# USB_ISO_FS_00.net
KiCad netlist of a schematic drawn in Altium Designer
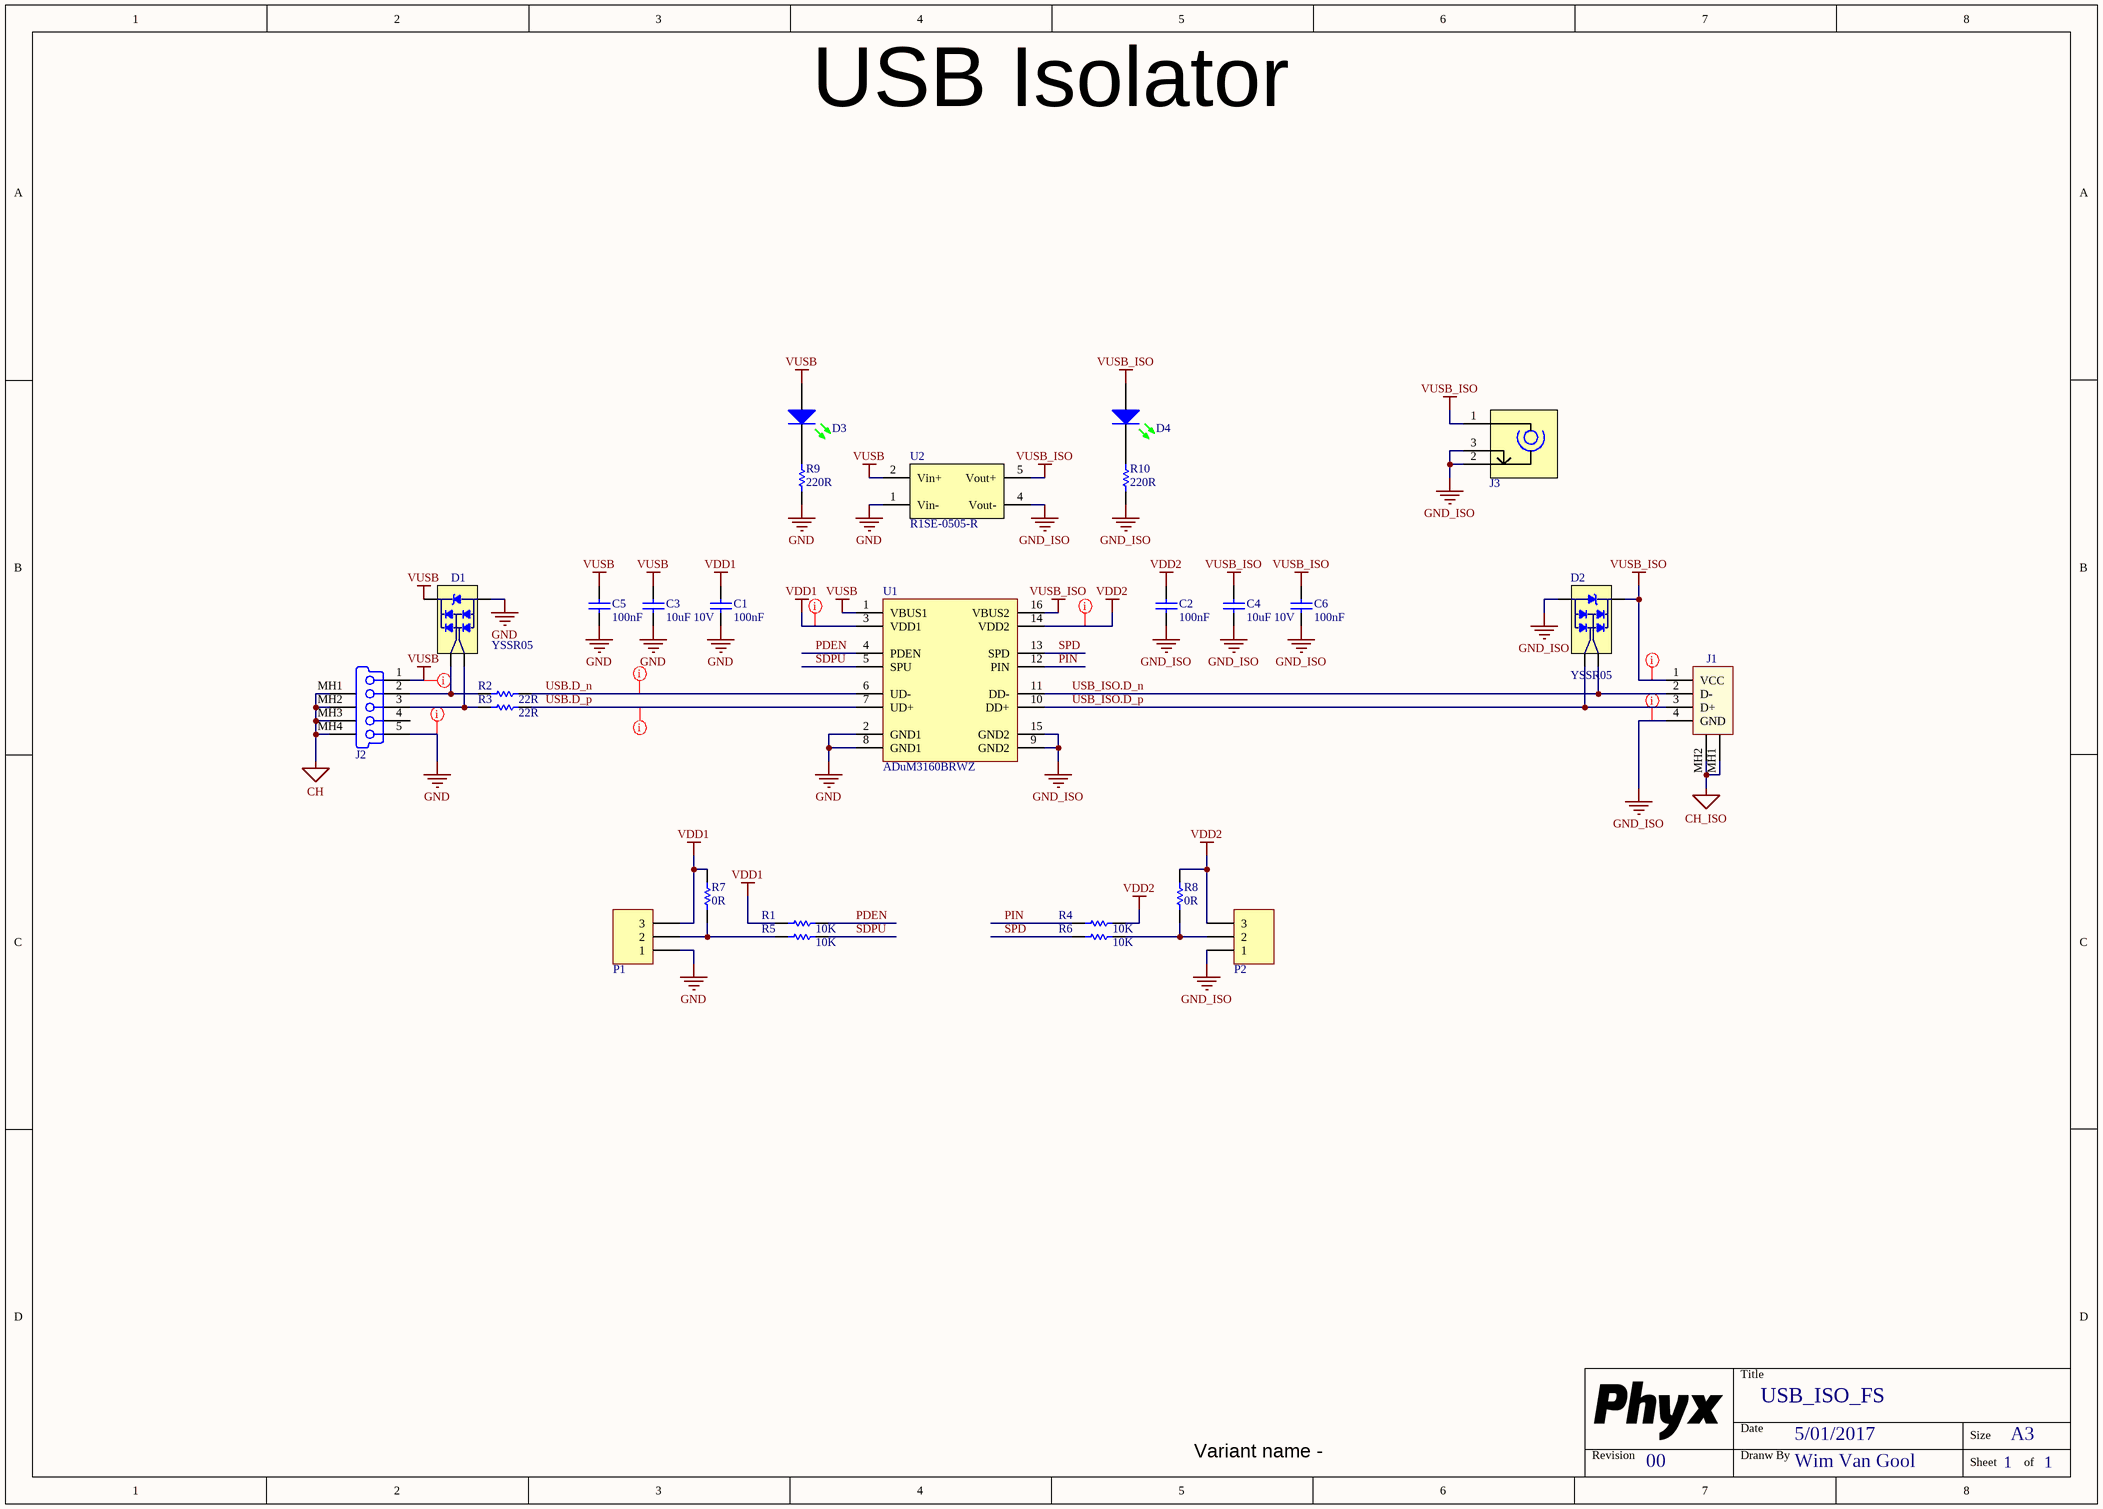
[diagram p0: USB_ISO_FS_00.SchDoc]

(export (version "E")
  (design (tool "Eeschema 10.0.6"))
  (components
    (comp (ref "C1")
      (value "100nF")
      (footprint "C0603_N")
      (description "CAP # 100nF 16V 0603")
      (fields (field (name "Comment") "CAP_CERAMIC"))
      (libsource (lib "Phyx_Components") (part "CAP_CERAMIC"))
    )
    (comp (ref "C2")
      (value "100nF")
      (footprint "C0603_N")
      (description "CAP # 100nF 16V 0603")
      (fields (field (name "Comment") "CAP_CERAMIC"))
      (libsource (lib "Phyx_Components") (part "CAP_CERAMIC"))
    )
    (comp (ref "C3")
      (value "10uF 10V")
      (footprint "C0805_N")
      (description "CAP # 10uF 10V 0805")
      (fields (field (name "Comment") "CAP_CERAMIC"))
      (libsource (lib "Phyx_Components") (part "CAP_CERAMIC"))
    )
    (comp (ref "C4")
      (value "10uF 10V")
      (footprint "C0805_N")
      (description "CAP # 10uF 10V 0805")
      (fields (field (name "Comment") "CAP_CERAMIC"))
      (libsource (lib "Phyx_Components") (part "CAP_CERAMIC"))
    )
    (comp (ref "C5")
      (value "100nF")
      (footprint "C0603_N")
      (description "CAP # 100nF 16V 0603")
      (fields (field (name "Comment") "CAP_CERAMIC"))
      (libsource (lib "Phyx_Components") (part "CAP_CERAMIC"))
    )
    (comp (ref "C6")
      (value "100nF")
      (footprint "C0603_N")
      (description "CAP # 100nF 16V 0603")
      (fields (field (name "Comment") "CAP_CERAMIC"))
      (libsource (lib "Phyx_Components") (part "CAP_CERAMIC"))
    )
    (comp (ref "D1")
      (value "YSSR05")
      (footprint "SOT-143")
      (description "=Description")
      (fields (field (name "Comment") "Low Capacitanse TVS Diode array"))
      (libsource (lib "") (part "YSSR05_1"))
    )
    (comp (ref "D2")
      (value "YSSR05")
      (footprint "SOT-143")
      (description "=Description")
      (fields (field (name "Comment") "Low Capacitanse TVS Diode array"))
      (libsource (lib "Phyx_Components") (part "YSSR05"))
    )
    (comp (ref "D3")
      (value "Default 0805 Green LED")
      (footprint "LED_0805_GR")
      (description "LED # Green 0805")
      (libsource (lib "Phyx_Components") (part "LED_GREEN"))
    )
    (comp (ref "D4")
      (value "Default 0805 Green LED")
      (footprint "LED_0805_GR")
      (description "LED # Green 0805")
      (libsource (lib "Phyx_Components") (part "LED_GREEN"))
    )
    (comp (ref "J1")
      (value "USB type A Short horizontal connector")
      (footprint "WE_614104150121")
      (description "USB A 614104150121 Short")
      (libsource (lib "Phyx_Components") (part "USB_A"))
    )
    (comp (ref "J2")
      (value "THT USB Mini-B Receptacle")
      (footprint "USB_Mini-B_THT")
      (description "USB Mini-B F")
      (libsource (lib "Phyx_Components") (part "USB_OTG_Mini-B"))
    )
    (comp (ref "J3")
      (value "Socket RA 3.5 with 1.35 barrel")
      (footprint "DC-003")
      (description "SCKT 1.35mm barrel 3.5mm dia")
      (libsource (lib "Phyx_Components") (part "Cliff_DC10"))
    )
    (comp (ref "P1")
      (value "Header 3")
      (footprint "HDR1X3")
      (description "Pin Header 2.54mm 3way")
      (libsource (lib "") (part "Header 3_1"))
    )
    (comp (ref "P2")
      (value "Header 3")
      (footprint "HDR1X3")
      (description "Pin Header 2.54mm 3way")
      (libsource (lib "Phyx_Components") (part "Header 3"))
    )
    (comp (ref "R1")
      (value "10K")
      (footprint "R0603_N")
      (description "RES # 10K 0603")
      (fields (field (name "Comment") "RESISTOR"))
      (libsource (lib "Phyx_Components") (part "RESISTOR"))
    )
    (comp (ref "R2")
      (value "22R")
      (footprint "R0603_N")
      (description "RES # 22R 0603")
      (fields (field (name "Comment") "RESISTOR"))
      (libsource (lib "Phyx_Components") (part "RESISTOR"))
    )
    (comp (ref "R3")
      (value "22R")
      (footprint "R0603_N")
      (description "RES # 22R 0603")
      (fields (field (name "Comment") "RESISTOR"))
      (libsource (lib "Phyx_Components") (part "RESISTOR"))
    )
    (comp (ref "R4")
      (value "10K")
      (footprint "R0603_N")
      (description "RES # 10K 0603")
      (fields (field (name "Comment") "RESISTOR"))
      (libsource (lib "Phyx_Components") (part "RESISTOR"))
    )
    (comp (ref "R5")
      (value "10K")
      (footprint "R0603_N")
      (description "RES # 10K 0603")
      (fields (field (name "Comment") "RESISTOR"))
      (libsource (lib "Phyx_Components") (part "RESISTOR"))
    )
    (comp (ref "R6")
      (value "10K")
      (footprint "R0603_N")
      (description "RES # 10K 0603")
      (fields (field (name "Comment") "RESISTOR"))
      (libsource (lib "Phyx_Components") (part "RESISTOR"))
    )
    (comp (ref "R7")
      (value "0R")
      (footprint "R0603_N")
      (description "RES # 0R 0603")
      (fields (field (name "Comment") "RESISTOR"))
      (libsource (lib "Phyx_Components") (part "RESISTOR"))
    )
    (comp (ref "R8")
      (value "0R")
      (footprint "R0603_N")
      (description "RES # 0R 0603")
      (fields (field (name "Comment") "RESISTOR"))
      (libsource (lib "Phyx_Components") (part "RESISTOR"))
    )
    (comp (ref "R9")
      (value "220R")
      (footprint "R0603_N")
      (description "RES # 220R 0603")
      (fields (field (name "Comment") "RESISTOR"))
      (libsource (lib "Phyx_Components") (part "RESISTOR"))
    )
    (comp (ref "R10")
      (value "220R")
      (footprint "R0603_N")
      (description "RES # 220R 0603")
      (fields (field (name "Comment") "RESISTOR"))
      (libsource (lib "Phyx_Components") (part "RESISTOR"))
    )
    (comp (ref "U1")
      (value "ADuM3160BRWZ")
      (footprint "SOIC_W_16")
      (description "ISO # USB ADuM3160BRWZ")
      (fields (field (name "Comment") "USB FS 12Mbps isolator 2,5kV"))
      (libsource (lib "Phyx_Components") (part "ADUM3160"))
    )
    (comp (ref "U2")
      (value "R1SE-0505-R")
      (footprint "R1SE-0505-R")
      (description "ISO # PWR 5V 1W 1kV R1SE-0505-R")
      (fields (field (name "Comment") "Isolated DC-DC module 1kV 5V 1W"))
      (libsource (lib "Phyx_Components") (part "R1SE-0505-R"))
    )
  )
  (nets
    (net (code "1") (name "/PDEN") (class "Default")
      (node (ref "R1") (pin "1") (pinfunction "1_1") (pintype "passive"))
      (node (ref "U1") (pin "4") (pinfunction "PDEN_4") (pintype "passive"))
    )
    (net (code "2") (name "/PIN") (class "Default")
      (node (ref "R4") (pin "2") (pinfunction "2_2") (pintype "passive"))
      (node (ref "U1") (pin "12") (pinfunction "PIN_12") (pintype "passive"))
    )
    (net (code "3") (name "/SDPU") (class "Default")
      (node (ref "R5") (pin "1") (pinfunction "1_1") (pintype "passive"))
      (node (ref "U1") (pin "5") (pinfunction "SPU_5") (pintype "passive"))
    )
    (net (code "4") (name "/SPD") (class "Default")
      (node (ref "R6") (pin "2") (pinfunction "2_2") (pintype "passive"))
      (node (ref "U1") (pin "13") (pinfunction "SPD_13") (pintype "passive"))
    )
    (net (code "5") (name "/USB.D_n") (class "Default")
      (node (ref "R2") (pin "1") (pinfunction "1_1") (pintype "passive"))
      (node (ref "U1") (pin "6") (pinfunction "UD-_6") (pintype "passive"))
    )
    (net (code "6") (name "/USB.D_p") (class "Default")
      (node (ref "R3") (pin "1") (pinfunction "1_1") (pintype "passive"))
      (node (ref "U1") (pin "7") (pinfunction "UD+_7") (pintype "passive"))
    )
    (net (code "7") (name "/USB_ISO.D_n") (class "Default")
      (node (ref "D2") (pin "3") (pinfunction "3_3") (pintype "passive"))
      (node (ref "J1") (pin "2") (pinfunction "D-_2") (pintype "passive"))
      (node (ref "U1") (pin "11") (pinfunction "DD-_11") (pintype "passive"))
    )
    (net (code "8") (name "/USB_ISO.D_p") (class "Default")
      (node (ref "D2") (pin "2") (pinfunction "2_2") (pintype "passive"))
      (node (ref "J1") (pin "3") (pinfunction "D+_3") (pintype "passive"))
      (node (ref "U1") (pin "10") (pinfunction "DD+_10") (pintype "passive"))
    )
    (net (code "9") (name "CH") (class "Default")
      (node (ref "J2") (pin "MH1") (pinfunction "Tab_MH1") (pintype "passive"))
      (node (ref "J2") (pin "MH2") (pinfunction "Tab_MH2") (pintype "passive"))
      (node (ref "J2") (pin "MH3") (pinfunction "Tab_MH3") (pintype "passive"))
      (node (ref "J2") (pin "MH4") (pinfunction "Tab_MH4") (pintype "passive"))
    )
    (net (code "10") (name "CH_ISO") (class "Default")
      (node (ref "J1") (pin "MH1") (pinfunction "Tab_MH1") (pintype "passive"))
      (node (ref "J1") (pin "MH2") (pinfunction "Tab_MH2") (pintype "passive"))
    )
    (net (code "11") (name "GND") (class "Default")
      (node (ref "C1") (pin "2") (pinfunction "2_2") (pintype "passive"))
      (node (ref "C3") (pin "2") (pinfunction "2_2") (pintype "passive"))
      (node (ref "C5") (pin "2") (pinfunction "2_2") (pintype "passive"))
      (node (ref "D1") (pin "1") (pinfunction "1_1") (pintype "passive"))
      (node (ref "J2") (pin "5") (pinfunction "GND_5") (pintype "passive"))
      (node (ref "P1") (pin "1") (pinfunction "1_1") (pintype "passive"))
      (node (ref "R9") (pin "2") (pinfunction "2_2") (pintype "passive"))
      (node (ref "U1") (pin "2") (pinfunction "GND1_2") (pintype "passive"))
      (node (ref "U1") (pin "8") (pinfunction "GND1_8") (pintype "passive"))
      (node (ref "U2") (pin "1") (pinfunction "Vin-_1") (pintype "power_in"))
    )
    (net (code "12") (name "GND_ISO") (class "Default")
      (node (ref "C2") (pin "2") (pinfunction "2_2") (pintype "passive"))
      (node (ref "C4") (pin "2") (pinfunction "2_2") (pintype "passive"))
      (node (ref "C6") (pin "2") (pinfunction "2_2") (pintype "passive"))
      (node (ref "D2") (pin "1") (pinfunction "1_1") (pintype "passive"))
      (node (ref "J1") (pin "4") (pinfunction "GND_4") (pintype "passive"))
      (node (ref "J3") (pin "2") (pinfunction "2_2") (pintype "passive"))
      (node (ref "J3") (pin "3") (pinfunction "3_3") (pintype "passive"))
      (node (ref "P2") (pin "1") (pinfunction "1_1") (pintype "passive"))
      (node (ref "R10") (pin "2") (pinfunction "2_2") (pintype "passive"))
      (node (ref "U1") (pin "15") (pinfunction "GND2_15") (pintype "passive"))
      (node (ref "U1") (pin "9") (pinfunction "GND2_9") (pintype "passive"))
      (node (ref "U2") (pin "4") (pinfunction "Vout-_4") (pintype "power_in"))
    )
    (net (code "13") (name "Net-(D3-K)") (class "Default")
      (node (ref "D3") (pin "2") (pinfunction "K_2") (pintype "passive"))
      (node (ref "R9") (pin "1") (pinfunction "1_1") (pintype "passive"))
    )
    (net (code "14") (name "Net-(D4-K)") (class "Default")
      (node (ref "D4") (pin "2") (pinfunction "K_2") (pintype "passive"))
      (node (ref "R10") (pin "1") (pinfunction "1_1") (pintype "passive"))
    )
    (net (code "15") (name "Net-(J2-D+)") (class "Default")
      (node (ref "D1") (pin "2") (pinfunction "2_2") (pintype "passive"))
      (node (ref "J2") (pin "3") (pinfunction "D+_3") (pintype "passive"))
      (node (ref "R3") (pin "2") (pinfunction "2_2") (pintype "passive"))
    )
    (net (code "16") (name "Net-(J2-D-)") (class "Default")
      (node (ref "D1") (pin "3") (pinfunction "3_3") (pintype "passive"))
      (node (ref "J2") (pin "2") (pinfunction "D-_2") (pintype "passive"))
      (node (ref "R2") (pin "2") (pinfunction "2_2") (pintype "passive"))
    )
    (net (code "17") (name "Net-(P1-Pad2)") (class "Default")
      (node (ref "P1") (pin "2") (pinfunction "2_2") (pintype "passive"))
      (node (ref "R5") (pin "2") (pinfunction "2_2") (pintype "passive"))
      (node (ref "R7") (pin "2") (pinfunction "2_2") (pintype "passive"))
    )
    (net (code "18") (name "Net-(P2-Pad2)") (class "Default")
      (node (ref "P2") (pin "2") (pinfunction "2_2") (pintype "passive"))
      (node (ref "R6") (pin "1") (pinfunction "1_1") (pintype "passive"))
      (node (ref "R8") (pin "2") (pinfunction "2_2") (pintype "passive"))
    )
    (net (code "19") (name "VDD1") (class "Default")
      (node (ref "C1") (pin "1") (pinfunction "1_1") (pintype "passive"))
      (node (ref "P1") (pin "3") (pinfunction "3_3") (pintype "passive"))
      (node (ref "R1") (pin "2") (pinfunction "2_2") (pintype "passive"))
      (node (ref "R7") (pin "1") (pinfunction "1_1") (pintype "passive"))
      (node (ref "U1") (pin "3") (pinfunction "VDD1_3") (pintype "passive"))
    )
    (net (code "20") (name "VDD2") (class "Default")
      (node (ref "C2") (pin "1") (pinfunction "1_1") (pintype "passive"))
      (node (ref "P2") (pin "3") (pinfunction "3_3") (pintype "passive"))
      (node (ref "R4") (pin "1") (pinfunction "1_1") (pintype "passive"))
      (node (ref "R8") (pin "1") (pinfunction "1_1") (pintype "passive"))
      (node (ref "U1") (pin "14") (pinfunction "VDD2_14") (pintype "passive"))
    )
    (net (code "21") (name "VUSB") (class "Default")
      (node (ref "C3") (pin "1") (pinfunction "1_1") (pintype "passive"))
      (node (ref "C5") (pin "1") (pinfunction "1_1") (pintype "passive"))
      (node (ref "D1") (pin "4") (pinfunction "4_4") (pintype "passive"))
      (node (ref "D3") (pin "1") (pinfunction "A_1") (pintype "passive"))
      (node (ref "J2") (pin "1") (pinfunction "V_BUS_(5V)_1") (pintype "passive"))
      (node (ref "U1") (pin "1") (pinfunction "VBUS1_1") (pintype "passive"))
      (node (ref "U2") (pin "2") (pinfunction "Vin+_2") (pintype "power_in"))
    )
    (net (code "22") (name "VUSB_ISO") (class "Default")
      (node (ref "C4") (pin "1") (pinfunction "1_1") (pintype "passive"))
      (node (ref "C6") (pin "1") (pinfunction "1_1") (pintype "passive"))
      (node (ref "D2") (pin "4") (pinfunction "4_4") (pintype "passive"))
      (node (ref "D4") (pin "1") (pinfunction "A_1") (pintype "passive"))
      (node (ref "J1") (pin "1") (pinfunction "VCC_1") (pintype "passive"))
      (node (ref "J3") (pin "1") (pinfunction "1_1") (pintype "passive"))
      (node (ref "U1") (pin "16") (pinfunction "VBUS2_16") (pintype "passive"))
      (node (ref "U2") (pin "5") (pinfunction "Vout+_5") (pintype "power_in"))
    )
    (net (code "23") (name "unconnected-(J2-NC-Pad4)") (class "Default")
      (node (ref "J2") (pin "4") (pinfunction "NC_4") (pintype "passive"))
    )
  )
)
